# Hockey_Table.net
KiCad netlist of a schematic drawn in EAGLE
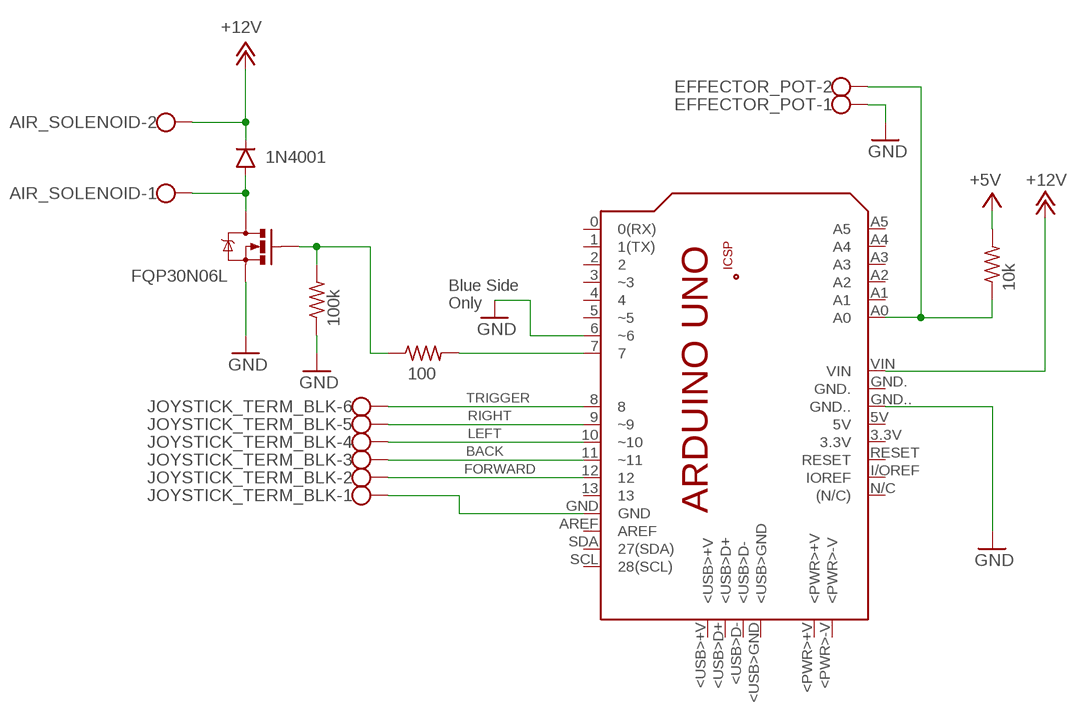
[diagram p0: schematic, sheet 1]

(export (version "E")
  (design (tool "Eeschema 10.0.6"))
  (components
    (comp (ref "AIR_SOLENOID")
      (value "TERMBLK_SCREW_2RIGHT")
      (footprint "eagle-import:TERMBLK_SCREW_2")
      (libsource (lib "eagle-import") (part "TERMBLK_SCREW_2RIGHT"))
    )
    (comp (ref "D1")
      (value "1N4001")
      (footprint "eagle-import:DIODE-1N4148")
      (libsource (lib "eagle-import") (part "DIODE1N4148"))
    )
    (comp (ref "EFFECTOR_POT")
      (value "TERMBLK_SCREW_2RIGHT")
      (footprint "eagle-import:TERMBLK_SCREW_2")
      (libsource (lib "eagle-import") (part "TERMBLK_SCREW_2RIGHT"))
    )
    (comp (ref "JOYSTICK_TERM_BLK")
      (value "TERMBLK_SCREW_6RIGHT")
      (footprint "eagle-import:TERMBLK_SCREW_6")
      (libsource (lib "eagle-import") (part "TERMBLK_SCREW_6RIGHT"))
    )
    (comp (ref "PCB1")
      (value "ARDUINO_UNO")
      (footprint "eagle-import:ARDUINO_UNO")
      (libsource (lib "eagle-import") (part "ARDUINO_UNO"))
    )
    (comp (ref "Q1")
      (value "FQP30N06L")
      (footprint "eagle-import:TO220V")
      (libsource (lib "eagle-import") (part "MOSFET-NCHANNELFQP30N06L"))
    )
    (comp (ref "R1")
      (value "10k")
      (footprint "eagle-import:0207_10")
      (libsource (lib "eagle-import") (part "R-US_0207/10"))
    )
    (comp (ref "R2")
      (value "100k")
      (footprint "eagle-import:0207_10")
      (libsource (lib "eagle-import") (part "R-US_0207/10"))
    )
    (comp (ref "R3")
      (value "100")
      (footprint "eagle-import:0207_10")
      (libsource (lib "eagle-import") (part "R-US_0207/10"))
    )
  )
  (nets
    (net (code "1") (name "+5V") (class "Default")
      (node (ref "R1") (pin "2") (pinfunction "2_2") (pintype "passive"))
    )
    (net (code "2") (name "+12V") (class "Default")
      (node (ref "AIR_SOLENOID") (pin "2") (pinfunction "1_2") (pintype "passive"))
      (node (ref "D1") (pin "C") (pinfunction "C_C") (pintype "passive"))
      (node (ref "PCB1") (pin "VIN") (pinfunction "VIN_VIN") (pintype "bidirectional"))
    )
    (net (code "3") (name "/BACK") (class "Default")
      (node (ref "JOYSTICK_TERM_BLK") (pin "3") (pinfunction "1_3") (pintype "passive"))
      (node (ref "PCB1") (pin "11") (pinfunction "~{11}_11") (pintype "bidirectional"))
    )
    (net (code "4") (name "/FORWARD") (class "Default")
      (node (ref "JOYSTICK_TERM_BLK") (pin "2") (pinfunction "1_2") (pintype "passive"))
      (node (ref "PCB1") (pin "12") (pinfunction "12_12") (pintype "bidirectional"))
    )
    (net (code "5") (name "/LEFT") (class "Default")
      (node (ref "JOYSTICK_TERM_BLK") (pin "4") (pinfunction "1_4") (pintype "passive"))
      (node (ref "PCB1") (pin "10") (pinfunction "~{10}_10") (pintype "bidirectional"))
    )
    (net (code "6") (name "/RIGHT") (class "Default")
      (node (ref "JOYSTICK_TERM_BLK") (pin "5") (pinfunction "1_5") (pintype "passive"))
      (node (ref "PCB1") (pin "9") (pinfunction "~{9}_9") (pintype "bidirectional"))
    )
    (net (code "7") (name "/TRIGGER") (class "Default")
      (node (ref "JOYSTICK_TERM_BLK") (pin "6") (pinfunction "1_6") (pintype "passive"))
      (node (ref "PCB1") (pin "8") (pinfunction "8_8") (pintype "bidirectional"))
    )
    (net (code "8") (name "GND") (class "Default")
      (node (ref "EFFECTOR_POT") (pin "1") (pinfunction "1_1") (pintype "passive"))
      (node (ref "PCB1") (pin "6") (pinfunction "~{6}_6") (pintype "bidirectional"))
      (node (ref "PCB1") (pin "GND..") (pinfunction "GND.._GND..") (pintype "bidirectional"))
      (node (ref "Q1") (pin "3") (pinfunction "S_3") (pintype "passive"))
      (node (ref "R2") (pin "1") (pinfunction "1_1") (pintype "passive"))
    )
    (net (code "9") (name "Net-(EFFECTOR_POTB-1)") (class "Default")
      (node (ref "EFFECTOR_POT") (pin "2") (pinfunction "1_2") (pintype "passive"))
      (node (ref "PCB1") (pin "A0") (pinfunction "A0_A0") (pintype "bidirectional"))
      (node (ref "R1") (pin "1") (pinfunction "1_1") (pintype "passive"))
    )
    (net (code "10") (name "Net-(JOYSTICK_TERM_BLK-Pad1)") (class "Default")
      (node (ref "JOYSTICK_TERM_BLK") (pin "1") (pinfunction "1_1") (pintype "passive"))
      (node (ref "PCB1") (pin "GND") (pinfunction "GND_GND") (pintype "bidirectional"))
    )
    (net (code "11") (name "Net-(PCB1-Pad7)") (class "Default")
      (node (ref "PCB1") (pin "7") (pinfunction "7_7") (pintype "bidirectional"))
      (node (ref "R3") (pin "2") (pinfunction "2_2") (pintype "passive"))
    )
    (net (code "12") (name "Net-(Q1-D)") (class "Default")
      (node (ref "AIR_SOLENOID") (pin "1") (pinfunction "1_1") (pintype "passive"))
      (node (ref "D1") (pin "A") (pinfunction "A_A") (pintype "passive"))
      (node (ref "Q1") (pin "2") (pinfunction "D_2") (pintype "passive"))
    )
    (net (code "13") (name "Net-(Q1-G)") (class "Default")
      (node (ref "Q1") (pin "1") (pinfunction "G_1") (pintype "passive"))
      (node (ref "R2") (pin "2") (pinfunction "2_2") (pintype "passive"))
      (node (ref "R3") (pin "1") (pinfunction "1_1") (pintype "passive"))
    )
    (net (code "14") (name "unconnected-(PCB1-(N{slash}C)-PadN{slash}C)") (class "Default")
      (node (ref "PCB1") (pin "N/C") (pinfunction "(N/C)_N/C") (pintype "bidirectional"))
    )
    (net (code "15") (name "unconnected-(PCB1-0(RX)-Pad0)") (class "Default")
      (node (ref "PCB1") (pin "0") (pinfunction "0(RX)_0") (pintype "bidirectional"))
    )
    (net (code "16") (name "unconnected-(PCB1-1(TX)-Pad1)") (class "Default")
      (node (ref "PCB1") (pin "1") (pinfunction "1(TX)_1") (pintype "bidirectional"))
    )
    (net (code "17") (name "unconnected-(PCB1-27(SDA)-PadSDA)") (class "Default")
      (node (ref "PCB1") (pin "SDA") (pinfunction "27(SDA)_SDA") (pintype "bidirectional"))
    )
    (net (code "18") (name "unconnected-(PCB1-28(SCL)-PadSCL)") (class "Default")
      (node (ref "PCB1") (pin "SCL") (pinfunction "28(SCL)_SCL") (pintype "bidirectional"))
    )
    (net (code "19") (name "unconnected-(PCB1-IOREF-PadI{slash}OREF)") (class "Default")
      (node (ref "PCB1") (pin "I/OREF") (pinfunction "IOREF_I/OREF") (pintype "bidirectional"))
    )
    (net (code "20") (name "unconnected-(PCB1-Pad+5V)") (class "Default")
      (node (ref "PCB1") (pin "+5V") (pinfunction "+5V_+5V") (pintype "bidirectional"))
    )
    (net (code "21") (name "unconnected-(PCB1-Pad2)") (class "Default")
      (node (ref "PCB1") (pin "2") (pinfunction "2_2") (pintype "bidirectional"))
    )
    (net (code "22") (name "unconnected-(PCB1-Pad3.3V)") (class "Default")
      (node (ref "PCB1") (pin "3.3V") (pinfunction "3.3V_3.3V") (pintype "bidirectional"))
    )
    (net (code "23") (name "unconnected-(PCB1-Pad4)") (class "Default")
      (node (ref "PCB1") (pin "4") (pinfunction "4_4") (pintype "bidirectional"))
    )
    (net (code "24") (name "unconnected-(PCB1-Pad5V)") (class "Default")
      (node (ref "PCB1") (pin "5V") (pinfunction "5V_5V") (pintype "bidirectional"))
    )
    (net (code "25") (name "unconnected-(PCB1-Pad13)") (class "Default")
      (node (ref "PCB1") (pin "13") (pinfunction "13_13") (pintype "bidirectional"))
    )
    (net (code "26") (name "unconnected-(PCB1-Pad<PWR>+V)") (class "Default")
      (node (ref "PCB1") (pin "<PWR>+V") (pinfunction "<PWR>+V_<PWR>+V") (pintype "bidirectional"))
    )
    (net (code "27") (name "unconnected-(PCB1-Pad<PWR>-V)") (class "Default")
      (node (ref "PCB1") (pin "<PWR>-V") (pinfunction "<PWR>-V_<PWR>-V") (pintype "bidirectional"))
    )
    (net (code "28") (name "unconnected-(PCB1-Pad<USB>+V)") (class "Default")
      (node (ref "PCB1") (pin "<USB>+V") (pinfunction "<USB>+V_<USB>+V") (pintype "bidirectional"))
    )
    (net (code "29") (name "unconnected-(PCB1-Pad<USB>D+)") (class "Default")
      (node (ref "PCB1") (pin "<USB>D+") (pinfunction "<USB>D+_<USB>D+") (pintype "bidirectional"))
    )
    (net (code "30") (name "unconnected-(PCB1-Pad<USB>D-)") (class "Default")
      (node (ref "PCB1") (pin "<USB>D-") (pinfunction "<USB>D-_<USB>D-") (pintype "bidirectional"))
    )
    (net (code "31") (name "unconnected-(PCB1-Pad<USB>GND)") (class "Default")
      (node (ref "PCB1") (pin "<USB>GND") (pinfunction "<USB>GND_<USB>GND") (pintype "bidirectional"))
    )
    (net (code "32") (name "unconnected-(PCB1-PadA1)") (class "Default")
      (node (ref "PCB1") (pin "A1") (pinfunction "A1_A1") (pintype "bidirectional"))
    )
    (net (code "33") (name "unconnected-(PCB1-PadA2)") (class "Default")
      (node (ref "PCB1") (pin "A2") (pinfunction "A2_A2") (pintype "bidirectional"))
    )
    (net (code "34") (name "unconnected-(PCB1-PadA3)") (class "Default")
      (node (ref "PCB1") (pin "A3") (pinfunction "A3_A3") (pintype "bidirectional"))
    )
    (net (code "35") (name "unconnected-(PCB1-PadA4)") (class "Default")
      (node (ref "PCB1") (pin "A4") (pinfunction "A4_A4") (pintype "bidirectional"))
    )
    (net (code "36") (name "unconnected-(PCB1-PadA5)") (class "Default")
      (node (ref "PCB1") (pin "A5") (pinfunction "A5_A5") (pintype "bidirectional"))
    )
    (net (code "37") (name "unconnected-(PCB1-PadAREF)") (class "Default")
      (node (ref "PCB1") (pin "AREF") (pinfunction "AREF_AREF") (pintype "bidirectional"))
    )
    (net (code "38") (name "unconnected-(PCB1-PadGND.)") (class "Default")
      (node (ref "PCB1") (pin "GND.") (pinfunction "GND._GND.") (pintype "bidirectional"))
    )
    (net (code "39") (name "unconnected-(PCB1-PadGND_)") (class "Default")
      (node (ref "PCB1") (pin "GND_") (pinfunction "GND__GND_") (pintype "bidirectional"))
    )
    (net (code "40") (name "unconnected-(PCB1-PadMISO)") (class "Default")
      (node (ref "PCB1") (pin "MISO") (pinfunction "MISO_MISO") (pintype "bidirectional"))
    )
    (net (code "41") (name "unconnected-(PCB1-PadMOSI)") (class "Default")
      (node (ref "PCB1") (pin "MOSI") (pinfunction "MOSI_MOSI") (pintype "bidirectional"))
    )
    (net (code "42") (name "unconnected-(PCB1-PadRESET)") (class "Default")
      (node (ref "PCB1") (pin "RESET") (pinfunction "RESET_RESET") (pintype "bidirectional"))
    )
    (net (code "43") (name "unconnected-(PCB1-PadRESET.)") (class "Default")
      (node (ref "PCB1") (pin "RESET.") (pinfunction "RESET._RESET.") (pintype "bidirectional"))
    )
    (net (code "44") (name "unconnected-(PCB1-PadSCK)") (class "Default")
      (node (ref "PCB1") (pin "SCK") (pinfunction "SCK_SCK") (pintype "bidirectional"))
    )
    (net (code "45") (name "unconnected-(PCB1-~{3}-Pad3)") (class "Default")
      (node (ref "PCB1") (pin "3") (pinfunction "~{3}_3") (pintype "bidirectional"))
    )
    (net (code "46") (name "unconnected-(PCB1-~{5}-Pad5)") (class "Default")
      (node (ref "PCB1") (pin "5") (pinfunction "~{5}_5") (pintype "bidirectional"))
    )
  )
)
